# BalloonFPC_2x8.net
KiCad netlist of a schematic drawn in EAGLE
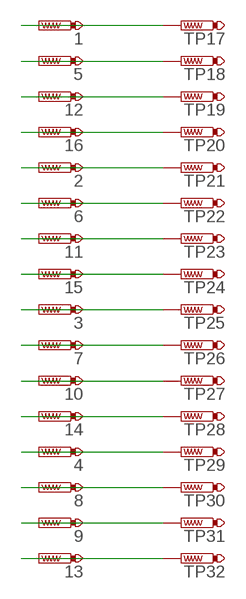
[diagram p0: schematic, sheet 1]

(export (version "E")
  (design (tool "Eeschema 10.0.6"))
  (components
    (comp (ref "1")
      (value "PTR11X2MM")
      (footprint "eagle-import:ELECPAD")
      (libsource (lib "eagle-import") (part "PTR11X2MM"))
    )
    (comp (ref "2")
      (value "PTR11X2MM")
      (footprint "eagle-import:ELECPAD")
      (libsource (lib "eagle-import") (part "PTR11X2MM"))
    )
    (comp (ref "3")
      (value "PTR11X2MM")
      (footprint "eagle-import:ELECPAD")
      (libsource (lib "eagle-import") (part "PTR11X2MM"))
    )
    (comp (ref "4")
      (value "PTR11X2MM")
      (footprint "eagle-import:ELECPAD")
      (libsource (lib "eagle-import") (part "PTR11X2MM"))
    )
    (comp (ref "5")
      (value "PTR11X2MM")
      (footprint "eagle-import:ELECPAD")
      (libsource (lib "eagle-import") (part "PTR11X2MM"))
    )
    (comp (ref "6")
      (value "PTR11X2MM")
      (footprint "eagle-import:ELECPAD")
      (libsource (lib "eagle-import") (part "PTR11X2MM"))
    )
    (comp (ref "7")
      (value "PTR11X2MM")
      (footprint "eagle-import:ELECPAD")
      (libsource (lib "eagle-import") (part "PTR11X2MM"))
    )
    (comp (ref "8")
      (value "PTR11X2MM")
      (footprint "eagle-import:ELECPAD")
      (libsource (lib "eagle-import") (part "PTR11X2MM"))
    )
    (comp (ref "9")
      (value "PTR11X2MM")
      (footprint "eagle-import:ELECPAD")
      (libsource (lib "eagle-import") (part "PTR11X2MM"))
    )
    (comp (ref "10")
      (value "PTR11X2MM")
      (footprint "eagle-import:ELECPAD")
      (libsource (lib "eagle-import") (part "PTR11X2MM"))
    )
    (comp (ref "11")
      (value "PTR11X2MM")
      (footprint "eagle-import:ELECPAD")
      (libsource (lib "eagle-import") (part "PTR11X2MM"))
    )
    (comp (ref "12")
      (value "PTR11X2MM")
      (footprint "eagle-import:ELECPAD")
      (libsource (lib "eagle-import") (part "PTR11X2MM"))
    )
    (comp (ref "13")
      (value "PTR11X2MM")
      (footprint "eagle-import:ELECPAD")
      (libsource (lib "eagle-import") (part "PTR11X2MM"))
    )
    (comp (ref "14")
      (value "PTR11X2MM")
      (footprint "eagle-import:ELECPAD")
      (libsource (lib "eagle-import") (part "PTR11X2MM"))
    )
    (comp (ref "15")
      (value "PTR11X2MM")
      (footprint "eagle-import:ELECPAD")
      (libsource (lib "eagle-import") (part "PTR11X2MM"))
    )
    (comp (ref "16")
      (value "PTR11X2MM")
      (footprint "eagle-import:ELECPAD")
      (libsource (lib "eagle-import") (part "PTR11X2MM"))
    )
    (comp (ref "TP17")
      (value "PTR1ZIF")
      (footprint "eagle-import:ZIFPAD")
      (libsource (lib "eagle-import") (part "PTR1ZIF"))
    )
    (comp (ref "TP18")
      (value "PTR1ZIF")
      (footprint "eagle-import:ZIFPAD")
      (libsource (lib "eagle-import") (part "PTR1ZIF"))
    )
    (comp (ref "TP19")
      (value "PTR1ZIF")
      (footprint "eagle-import:ZIFPAD")
      (libsource (lib "eagle-import") (part "PTR1ZIF"))
    )
    (comp (ref "TP20")
      (value "PTR1ZIF")
      (footprint "eagle-import:ZIFPAD")
      (libsource (lib "eagle-import") (part "PTR1ZIF"))
    )
    (comp (ref "TP21")
      (value "PTR1ZIF")
      (footprint "eagle-import:ZIFPAD")
      (libsource (lib "eagle-import") (part "PTR1ZIF"))
    )
    (comp (ref "TP22")
      (value "PTR1ZIF")
      (footprint "eagle-import:ZIFPAD")
      (libsource (lib "eagle-import") (part "PTR1ZIF"))
    )
    (comp (ref "TP23")
      (value "PTR1ZIF")
      (footprint "eagle-import:ZIFPAD")
      (libsource (lib "eagle-import") (part "PTR1ZIF"))
    )
    (comp (ref "TP24")
      (value "PTR1ZIF")
      (footprint "eagle-import:ZIFPAD")
      (libsource (lib "eagle-import") (part "PTR1ZIF"))
    )
    (comp (ref "TP25")
      (value "PTR1ZIF")
      (footprint "eagle-import:ZIFPAD")
      (libsource (lib "eagle-import") (part "PTR1ZIF"))
    )
    (comp (ref "TP26")
      (value "PTR1ZIF")
      (footprint "eagle-import:ZIFPAD")
      (libsource (lib "eagle-import") (part "PTR1ZIF"))
    )
    (comp (ref "TP27")
      (value "PTR1ZIF")
      (footprint "eagle-import:ZIFPAD")
      (libsource (lib "eagle-import") (part "PTR1ZIF"))
    )
    (comp (ref "TP28")
      (value "PTR1ZIF")
      (footprint "eagle-import:ZIFPAD")
      (libsource (lib "eagle-import") (part "PTR1ZIF"))
    )
    (comp (ref "TP29")
      (value "PTR1ZIF")
      (footprint "eagle-import:ZIFPAD")
      (libsource (lib "eagle-import") (part "PTR1ZIF"))
    )
    (comp (ref "TP30")
      (value "PTR1ZIF")
      (footprint "eagle-import:ZIFPAD")
      (libsource (lib "eagle-import") (part "PTR1ZIF"))
    )
    (comp (ref "TP31")
      (value "PTR1ZIF")
      (footprint "eagle-import:ZIFPAD")
      (libsource (lib "eagle-import") (part "PTR1ZIF"))
    )
    (comp (ref "TP32")
      (value "PTR1ZIF")
      (footprint "eagle-import:ZIFPAD")
      (libsource (lib "eagle-import") (part "PTR1ZIF"))
    )
  )
  (nets
    (net (code "1") (name "Net-(1-PadTP)") (class "Default")
      (node (ref "1") (pin "TP") (pinfunction "TP_TP") (pintype "input"))
      (node (ref "TP17") (pin "TP") (pinfunction "TP_TP") (pintype "input"))
    )
    (net (code "2") (name "Net-(2-PadTP)") (class "Default")
      (node (ref "2") (pin "TP") (pinfunction "TP_TP") (pintype "input"))
      (node (ref "TP21") (pin "TP") (pinfunction "TP_TP") (pintype "input"))
    )
    (net (code "3") (name "Net-(3-PadTP)") (class "Default")
      (node (ref "3") (pin "TP") (pinfunction "TP_TP") (pintype "input"))
      (node (ref "TP25") (pin "TP") (pinfunction "TP_TP") (pintype "input"))
    )
    (net (code "4") (name "Net-(4-PadTP)") (class "Default")
      (node (ref "4") (pin "TP") (pinfunction "TP_TP") (pintype "input"))
      (node (ref "TP29") (pin "TP") (pinfunction "TP_TP") (pintype "input"))
    )
    (net (code "5") (name "Net-(5-PadTP)") (class "Default")
      (node (ref "5") (pin "TP") (pinfunction "TP_TP") (pintype "input"))
      (node (ref "TP18") (pin "TP") (pinfunction "TP_TP") (pintype "input"))
    )
    (net (code "6") (name "Net-(6-PadTP)") (class "Default")
      (node (ref "6") (pin "TP") (pinfunction "TP_TP") (pintype "input"))
      (node (ref "TP22") (pin "TP") (pinfunction "TP_TP") (pintype "input"))
    )
    (net (code "7") (name "Net-(7-PadTP)") (class "Default")
      (node (ref "7") (pin "TP") (pinfunction "TP_TP") (pintype "input"))
      (node (ref "TP26") (pin "TP") (pinfunction "TP_TP") (pintype "input"))
    )
    (net (code "8") (name "Net-(8-PadTP)") (class "Default")
      (node (ref "8") (pin "TP") (pinfunction "TP_TP") (pintype "input"))
      (node (ref "TP30") (pin "TP") (pinfunction "TP_TP") (pintype "input"))
    )
    (net (code "9") (name "Net-(9-PadTP)") (class "Default")
      (node (ref "9") (pin "TP") (pinfunction "TP_TP") (pintype "input"))
      (node (ref "TP31") (pin "TP") (pinfunction "TP_TP") (pintype "input"))
    )
    (net (code "10") (name "Net-(10-PadTP)") (class "Default")
      (node (ref "10") (pin "TP") (pinfunction "TP_TP") (pintype "input"))
      (node (ref "TP27") (pin "TP") (pinfunction "TP_TP") (pintype "input"))
    )
    (net (code "11") (name "Net-(11-PadTP)") (class "Default")
      (node (ref "11") (pin "TP") (pinfunction "TP_TP") (pintype "input"))
      (node (ref "TP23") (pin "TP") (pinfunction "TP_TP") (pintype "input"))
    )
    (net (code "12") (name "Net-(12-PadTP)") (class "Default")
      (node (ref "12") (pin "TP") (pinfunction "TP_TP") (pintype "input"))
      (node (ref "TP19") (pin "TP") (pinfunction "TP_TP") (pintype "input"))
    )
    (net (code "13") (name "Net-(13-PadTP)") (class "Default")
      (node (ref "13") (pin "TP") (pinfunction "TP_TP") (pintype "input"))
      (node (ref "TP32") (pin "TP") (pinfunction "TP_TP") (pintype "input"))
    )
    (net (code "14") (name "Net-(14-PadTP)") (class "Default")
      (node (ref "14") (pin "TP") (pinfunction "TP_TP") (pintype "input"))
      (node (ref "TP28") (pin "TP") (pinfunction "TP_TP") (pintype "input"))
    )
    (net (code "15") (name "Net-(15-PadTP)") (class "Default")
      (node (ref "15") (pin "TP") (pinfunction "TP_TP") (pintype "input"))
      (node (ref "TP24") (pin "TP") (pinfunction "TP_TP") (pintype "input"))
    )
    (net (code "16") (name "Net-(16-PadTP)") (class "Default")
      (node (ref "16") (pin "TP") (pinfunction "TP_TP") (pintype "input"))
      (node (ref "TP20") (pin "TP") (pinfunction "TP_TP") (pintype "input"))
    )
  )
)
